# Board1_V3_singleSIded.net
KiCad netlist of a schematic drawn in EAGLE
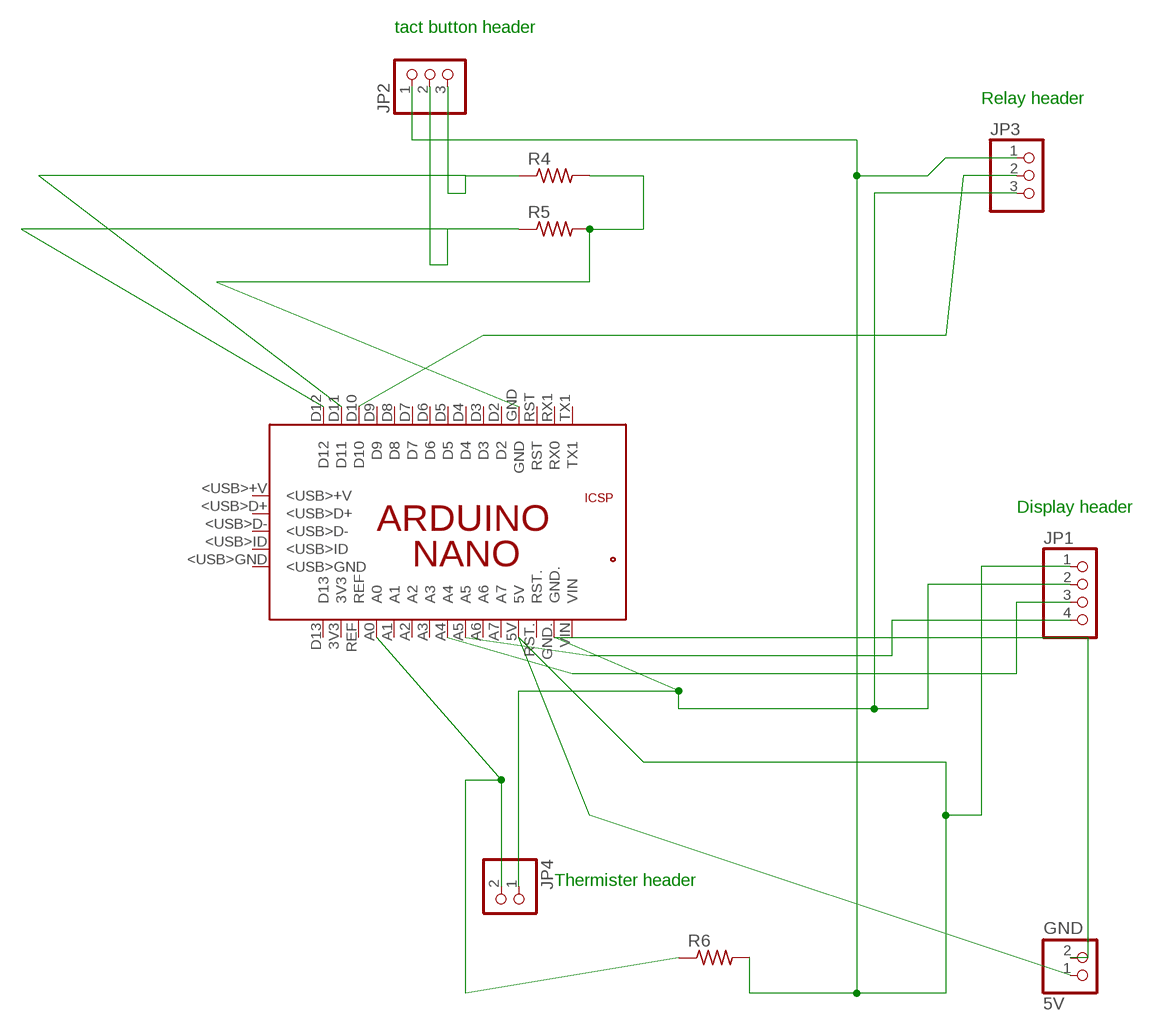
[diagram p0: schematic, sheet 1]

(export (version "E")
  (design (tool "Eeschema 10.0.6"))
  (components
    (comp (ref "5V")
      (value "GND")
      (footprint "eagle-import:1X02_90")
      (libsource (lib "eagle-import") (part "PINHD-1X2/90"))
    )
    (comp (ref "JP1")
      (value "PINHD-1X4/90")
      (footprint "eagle-import:1X04_90")
      (libsource (lib "eagle-import") (part "PINHD-1X4/90"))
    )
    (comp (ref "JP2")
      (value "PINHD-1X3/90")
      (footprint "eagle-import:1X03_90")
      (libsource (lib "eagle-import") (part "PINHD-1X3/90"))
    )
    (comp (ref "JP3")
      (value "PINHD-1X3/90")
      (footprint "eagle-import:1X03_90")
      (libsource (lib "eagle-import") (part "PINHD-1X3/90"))
    )
    (comp (ref "JP4")
      (value "PINHD-1X2/90")
      (footprint "eagle-import:1X02_90")
      (libsource (lib "eagle-import") (part "PINHD-1X2/90"))
    )
    (comp (ref "PCB1")
      (value "ARDUINO_NANO")
      (footprint "eagle-import:ARDUINO_NANO")
      (libsource (lib "eagle-import") (part "ARDUINO_NANO"))
    )
    (comp (ref "R4")
      (value "R-US_0207/10")
      (footprint "eagle-import:0207_10")
      (libsource (lib "eagle-import") (part "R-US_0207/10"))
    )
    (comp (ref "R5")
      (value "R-US_0207/10")
      (footprint "eagle-import:0207_10")
      (libsource (lib "eagle-import") (part "R-US_0207/10"))
    )
    (comp (ref "R6")
      (value "R-US_0207/15")
      (footprint "eagle-import:0207_15")
      (libsource (lib "eagle-import") (part "R-US_0207/15"))
    )
  )
  (nets
    (net (code "1") (name "Net-(5V-Pad1)") (class "Default")
      (node (ref "5V") (pin "1") (pinfunction "1_1") (pintype "passive"))
      (node (ref "JP1") (pin "1") (pinfunction "1_1") (pintype "passive"))
      (node (ref "JP2") (pin "1") (pinfunction "1_1") (pintype "passive"))
      (node (ref "JP3") (pin "1") (pinfunction "1_1") (pintype "passive"))
      (node (ref "PCB1") (pin "5V") (pinfunction "5V_5V") (pintype "bidirectional"))
      (node (ref "R6") (pin "2") (pinfunction "2_2") (pintype "passive"))
    )
    (net (code "2") (name "Net-(5V-Pad2)") (class "Default")
      (node (ref "5V") (pin "2") (pinfunction "2_2") (pintype "passive"))
      (node (ref "JP1") (pin "2") (pinfunction "2_2") (pintype "passive"))
      (node (ref "JP3") (pin "3") (pinfunction "3_3") (pintype "passive"))
      (node (ref "JP4") (pin "1") (pinfunction "1_1") (pintype "passive"))
      (node (ref "PCB1") (pin "GND.") (pinfunction "GND._GND.") (pintype "bidirectional"))
    )
    (net (code "3") (name "Net-(JP1-Pad3)") (class "Default")
      (node (ref "JP1") (pin "3") (pinfunction "3_3") (pintype "passive"))
      (node (ref "PCB1") (pin "A4") (pinfunction "A4_A4") (pintype "bidirectional"))
    )
    (net (code "4") (name "Net-(JP1-Pad4)") (class "Default")
      (node (ref "JP1") (pin "4") (pinfunction "4_4") (pintype "passive"))
      (node (ref "PCB1") (pin "A5") (pinfunction "A5_A5") (pintype "bidirectional"))
    )
    (net (code "5") (name "Net-(JP2-Pad2)") (class "Default")
      (node (ref "JP2") (pin "2") (pinfunction "2_2") (pintype "passive"))
      (node (ref "PCB1") (pin "D12") (pinfunction "D12_D12") (pintype "bidirectional"))
      (node (ref "R5") (pin "1") (pinfunction "1_1") (pintype "passive"))
    )
    (net (code "6") (name "Net-(JP2-Pad3)") (class "Default")
      (node (ref "JP2") (pin "3") (pinfunction "3_3") (pintype "passive"))
      (node (ref "PCB1") (pin "D11") (pinfunction "D11_D11") (pintype "bidirectional"))
      (node (ref "R4") (pin "1") (pinfunction "1_1") (pintype "passive"))
    )
    (net (code "7") (name "Net-(JP3-Pad2)") (class "Default")
      (node (ref "JP3") (pin "2") (pinfunction "2_2") (pintype "passive"))
      (node (ref "PCB1") (pin "D10") (pinfunction "D10_D10") (pintype "bidirectional"))
    )
    (net (code "8") (name "Net-(JP4-Pad2)") (class "Default")
      (node (ref "JP4") (pin "2") (pinfunction "2_2") (pintype "passive"))
      (node (ref "PCB1") (pin "A0") (pinfunction "A0_A0") (pintype "bidirectional"))
      (node (ref "R6") (pin "1") (pinfunction "1_1") (pintype "passive"))
    )
    (net (code "9") (name "Net-(PCB1-PadGND)") (class "Default")
      (node (ref "PCB1") (pin "GND") (pinfunction "GND_GND") (pintype "bidirectional"))
      (node (ref "R4") (pin "2") (pinfunction "2_2") (pintype "passive"))
      (node (ref "R5") (pin "2") (pinfunction "2_2") (pintype "passive"))
    )
    (net (code "10") (name "unconnected-(PCB1-Pad3V3)") (class "Default")
      (node (ref "PCB1") (pin "3V3") (pinfunction "3V3_3V3") (pintype "bidirectional"))
    )
    (net (code "11") (name "unconnected-(PCB1-Pad5V.)") (class "Default")
      (node (ref "PCB1") (pin "5V.") (pinfunction "5V._5V.") (pintype "bidirectional"))
    )
    (net (code "12") (name "unconnected-(PCB1-Pad<USB>+V)") (class "Default")
      (node (ref "PCB1") (pin "<USB>+V") (pinfunction "<USB>+V_<USB>+V") (pintype "bidirectional"))
    )
    (net (code "13") (name "unconnected-(PCB1-Pad<USB>D+)") (class "Default")
      (node (ref "PCB1") (pin "<USB>D+") (pinfunction "<USB>D+_<USB>D+") (pintype "bidirectional"))
    )
    (net (code "14") (name "unconnected-(PCB1-Pad<USB>D-)") (class "Default")
      (node (ref "PCB1") (pin "<USB>D-") (pinfunction "<USB>D-_<USB>D-") (pintype "bidirectional"))
    )
    (net (code "15") (name "unconnected-(PCB1-Pad<USB>GND)") (class "Default")
      (node (ref "PCB1") (pin "<USB>GND") (pinfunction "<USB>GND_<USB>GND") (pintype "bidirectional"))
    )
    (net (code "16") (name "unconnected-(PCB1-Pad<USB>ID)") (class "Default")
      (node (ref "PCB1") (pin "<USB>ID") (pinfunction "<USB>ID_<USB>ID") (pintype "bidirectional"))
    )
    (net (code "17") (name "unconnected-(PCB1-PadA1)") (class "Default")
      (node (ref "PCB1") (pin "A1") (pinfunction "A1_A1") (pintype "bidirectional"))
    )
    (net (code "18") (name "unconnected-(PCB1-PadA2)") (class "Default")
      (node (ref "PCB1") (pin "A2") (pinfunction "A2_A2") (pintype "bidirectional"))
    )
    (net (code "19") (name "unconnected-(PCB1-PadA3)") (class "Default")
      (node (ref "PCB1") (pin "A3") (pinfunction "A3_A3") (pintype "bidirectional"))
    )
    (net (code "20") (name "unconnected-(PCB1-PadA6)") (class "Default")
      (node (ref "PCB1") (pin "A6") (pinfunction "A6_A6") (pintype "bidirectional"))
    )
    (net (code "21") (name "unconnected-(PCB1-PadA7)") (class "Default")
      (node (ref "PCB1") (pin "A7") (pinfunction "A7_A7") (pintype "bidirectional"))
    )
    (net (code "22") (name "unconnected-(PCB1-PadD2)") (class "Default")
      (node (ref "PCB1") (pin "D2") (pinfunction "D2_D2") (pintype "bidirectional"))
    )
    (net (code "23") (name "unconnected-(PCB1-PadD3)") (class "Default")
      (node (ref "PCB1") (pin "D3") (pinfunction "D3_D3") (pintype "bidirectional"))
    )
    (net (code "24") (name "unconnected-(PCB1-PadD4)") (class "Default")
      (node (ref "PCB1") (pin "D4") (pinfunction "D4_D4") (pintype "bidirectional"))
    )
    (net (code "25") (name "unconnected-(PCB1-PadD5)") (class "Default")
      (node (ref "PCB1") (pin "D5") (pinfunction "D5_D5") (pintype "bidirectional"))
    )
    (net (code "26") (name "unconnected-(PCB1-PadD6)") (class "Default")
      (node (ref "PCB1") (pin "D6") (pinfunction "D6_D6") (pintype "bidirectional"))
    )
    (net (code "27") (name "unconnected-(PCB1-PadD7)") (class "Default")
      (node (ref "PCB1") (pin "D7") (pinfunction "D7_D7") (pintype "bidirectional"))
    )
    (net (code "28") (name "unconnected-(PCB1-PadD8)") (class "Default")
      (node (ref "PCB1") (pin "D8") (pinfunction "D8_D8") (pintype "bidirectional"))
    )
    (net (code "29") (name "unconnected-(PCB1-PadD9)") (class "Default")
      (node (ref "PCB1") (pin "D9") (pinfunction "D9_D9") (pintype "bidirectional"))
    )
    (net (code "30") (name "unconnected-(PCB1-PadD13)") (class "Default")
      (node (ref "PCB1") (pin "D13") (pinfunction "D13_D13") (pintype "bidirectional"))
    )
    (net (code "31") (name "unconnected-(PCB1-PadGND_)") (class "Default")
      (node (ref "PCB1") (pin "GND_") (pinfunction "GND__GND_") (pintype "bidirectional"))
    )
    (net (code "32") (name "unconnected-(PCB1-PadMISO)") (class "Default")
      (node (ref "PCB1") (pin "MISO") (pinfunction "MISO_MISO") (pintype "bidirectional"))
    )
    (net (code "33") (name "unconnected-(PCB1-PadMOSI)") (class "Default")
      (node (ref "PCB1") (pin "MOSI") (pinfunction "MOSI_MOSI") (pintype "bidirectional"))
    )
    (net (code "34") (name "unconnected-(PCB1-PadREF)") (class "Default")
      (node (ref "PCB1") (pin "REF") (pinfunction "REF_REF") (pintype "bidirectional"))
    )
    (net (code "35") (name "unconnected-(PCB1-PadRESET..)") (class "Default")
      (node (ref "PCB1") (pin "RESET..") (pinfunction "RESET.._RESET..") (pintype "bidirectional"))
    )
    (net (code "36") (name "unconnected-(PCB1-PadRST)") (class "Default")
      (node (ref "PCB1") (pin "RST") (pinfunction "RST_RST") (pintype "bidirectional"))
    )
    (net (code "37") (name "unconnected-(PCB1-PadRST.)") (class "Default")
      (node (ref "PCB1") (pin "RST.") (pinfunction "RST._RST.") (pintype "bidirectional"))
    )
    (net (code "38") (name "unconnected-(PCB1-PadSCK)") (class "Default")
      (node (ref "PCB1") (pin "SCK") (pinfunction "SCK_SCK") (pintype "bidirectional"))
    )
    (net (code "39") (name "unconnected-(PCB1-PadTX1)") (class "Default")
      (node (ref "PCB1") (pin "TX1") (pinfunction "TX1_TX1") (pintype "bidirectional"))
    )
    (net (code "40") (name "unconnected-(PCB1-PadVIN)") (class "Default")
      (node (ref "PCB1") (pin "VIN") (pinfunction "VIN_VIN") (pintype "bidirectional"))
    )
    (net (code "41") (name "unconnected-(PCB1-RX0-PadRX1)") (class "Default")
      (node (ref "PCB1") (pin "RX1") (pinfunction "RX0_RX1") (pintype "bidirectional"))
    )
  )
)
